# PSU.net
KiCad netlist of a schematic drawn in EAGLE
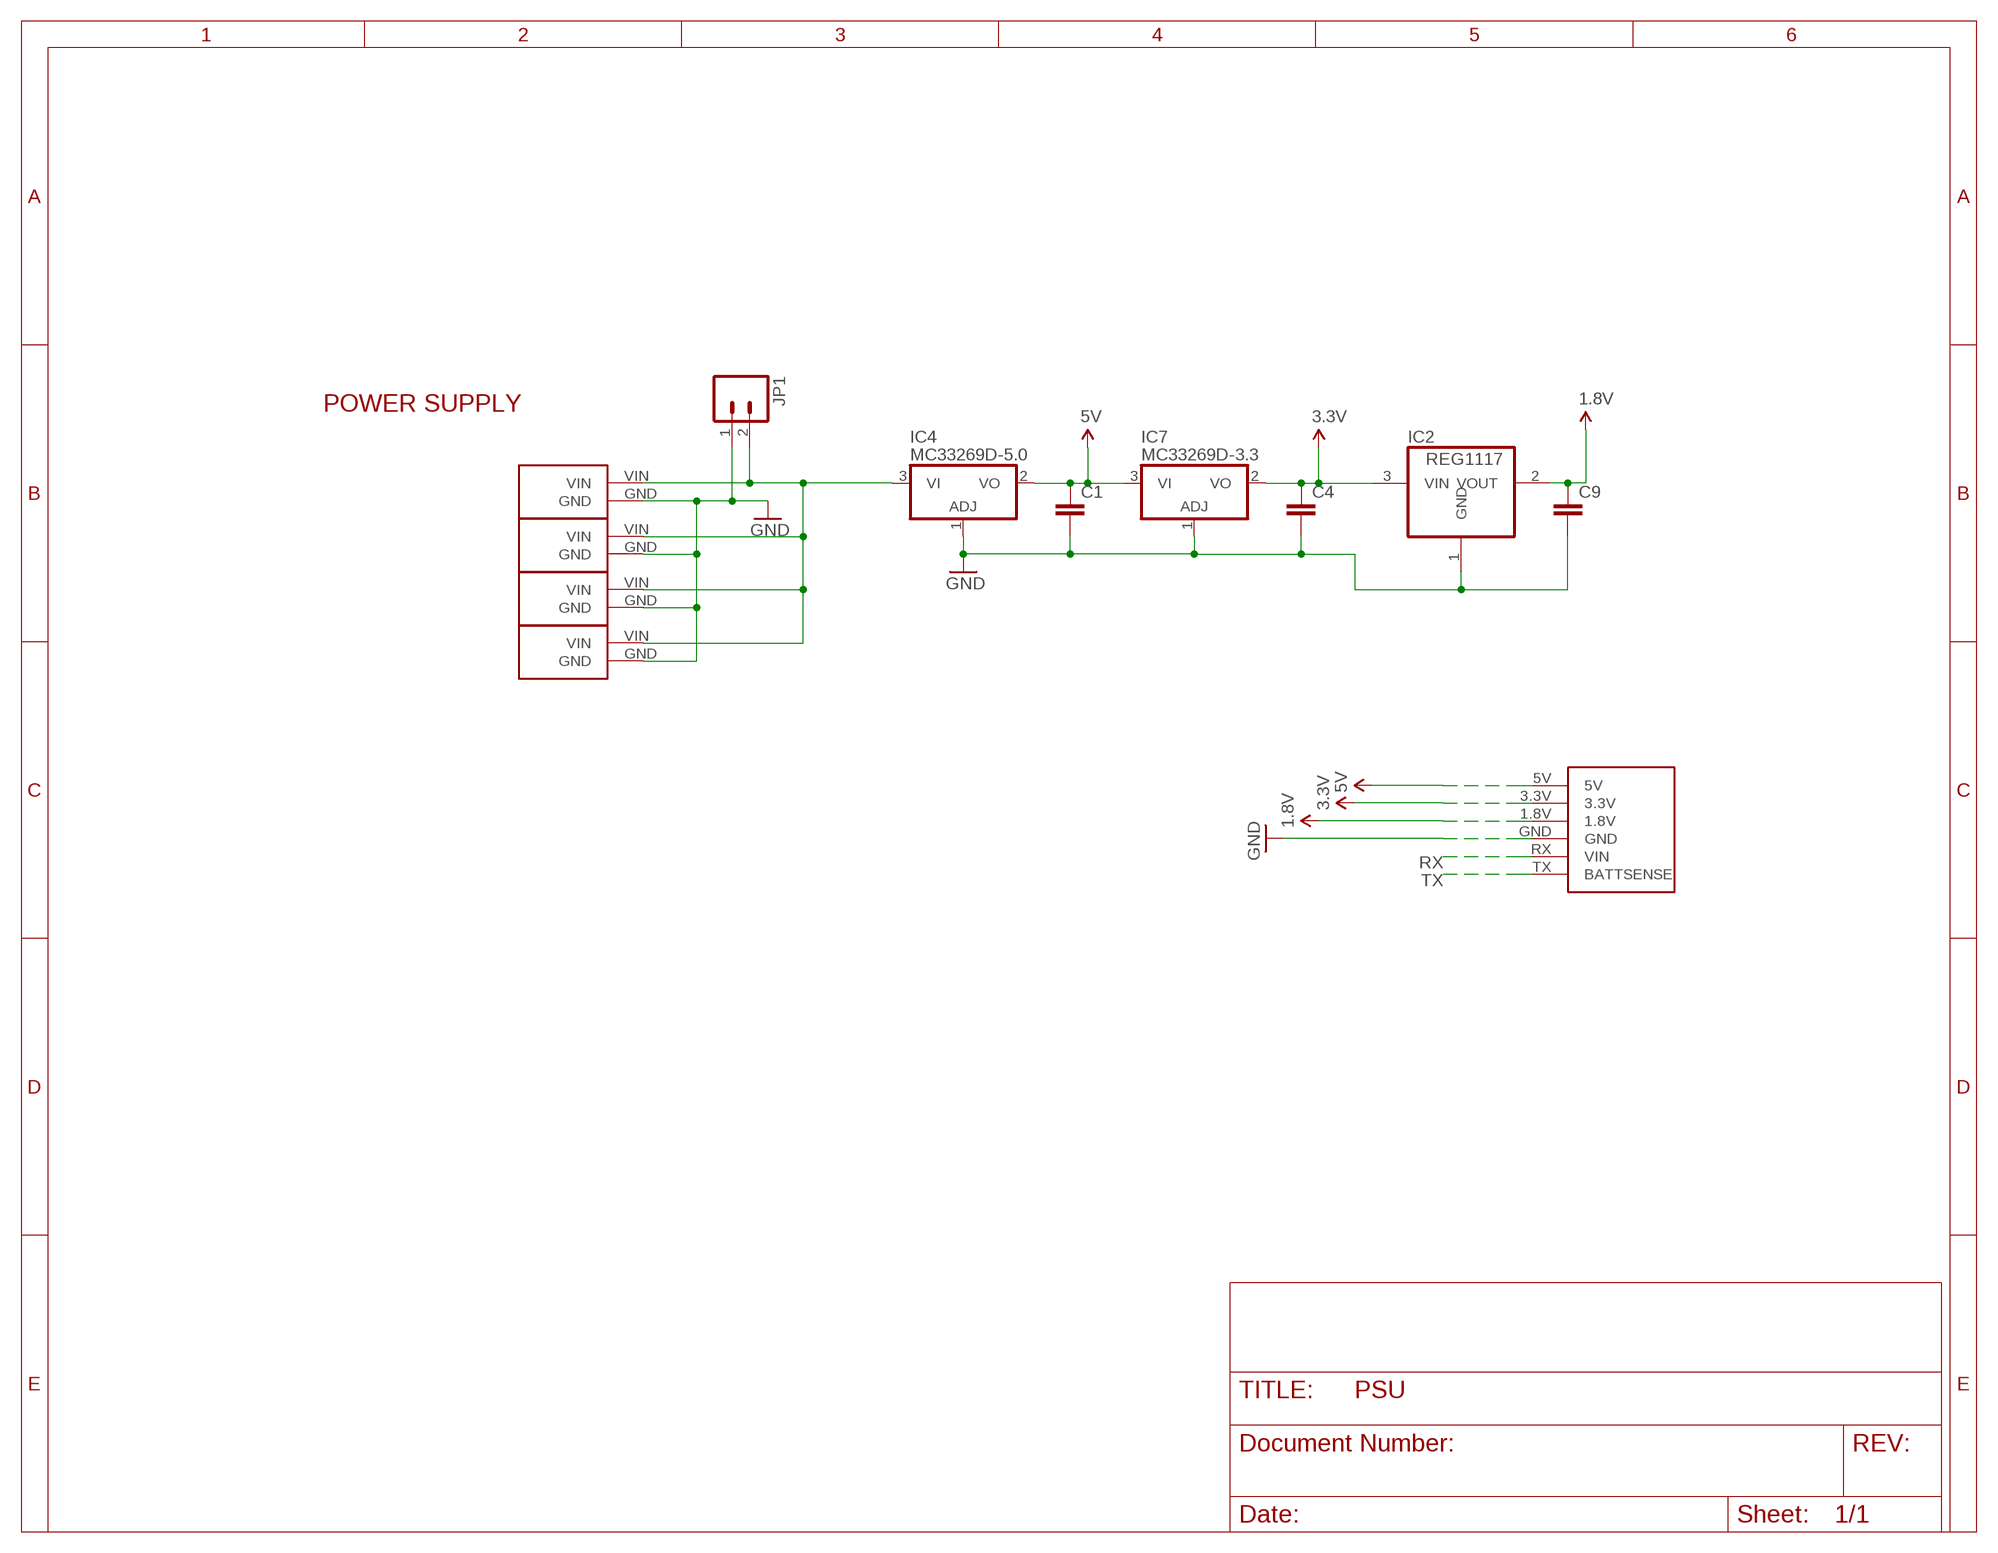
[diagram p0: schematic, sheet 1]

(export (version "E")
  (design (tool "Eeschema 10.0.6"))
  (components
    (comp (ref "C1")
      (value "CAP0805")
      (footprint "eagle-import:0805")
      (libsource (lib "eagle-import") (part "CAP0805"))
    )
    (comp (ref "C4")
      (value "CAP0805")
      (footprint "eagle-import:0805")
      (libsource (lib "eagle-import") (part "CAP0805"))
    )
    (comp (ref "C9")
      (value "CAP0805")
      (footprint "eagle-import:0805")
      (libsource (lib "eagle-import") (part "CAP0805"))
    )
    (comp (ref "IC2")
      (value "REG1117")
      (footprint "eagle-import:SOT223")
      (libsource (lib "eagle-import") (part "REG1117"))
    )
    (comp (ref "IC4")
      (value "MC33269D-5.0")
      (footprint "eagle-import:DPACK")
      (libsource (lib "eagle-import") (part "MC33269?D-5.0"))
    )
    (comp (ref "IC7")
      (value "MC33269D-3.3")
      (footprint "eagle-import:DPACK")
      (libsource (lib "eagle-import") (part "MC33269?D-3.3"))
    )
    (comp (ref "JP1")
      (value "M02PTH4")
      (footprint "eagle-import:1X02_XTRA_BIG")
      (libsource (lib "eagle-import") (part "M02PTH4"))
    )
    (comp (ref "QB1")
      (value "QUADBOARD")
      (footprint "eagle-import:QUADBOARD")
      (libsource (lib "eagle-import") (part "QUADBOARD"))
    )
    (comp (ref "U$2")
      (value "ESC_POWER")
      (footprint "eagle-import:ESCPOWER")
      (libsource (lib "eagle-import") (part "ESC_POWER"))
    )
    (comp (ref "U$3")
      (value "ESC_POWER")
      (footprint "eagle-import:ESCPOWER")
      (libsource (lib "eagle-import") (part "ESC_POWER"))
    )
    (comp (ref "U$4")
      (value "ESC_POWER")
      (footprint "eagle-import:ESCPOWER")
      (libsource (lib "eagle-import") (part "ESC_POWER"))
    )
    (comp (ref "U$5")
      (value "ESC_POWER")
      (footprint "eagle-import:ESCPOWER")
      (libsource (lib "eagle-import") (part "ESC_POWER"))
    )
  )
  (nets
    (net (code "1") (name "/RX") (class "Default")
      (node (ref "QB1") (pin "RX") (pinfunction "VIN_RX") (pintype "bidirectional"))
    )
    (net (code "2") (name "/TX") (class "Default")
      (node (ref "QB1") (pin "TX") (pinfunction "BATTSENSE_TX") (pintype "bidirectional"))
    )
    (net (code "3") (name "1.8V") (class "Default")
      (node (ref "C9") (pin "1") (pinfunction "1_1") (pintype "passive"))
      (node (ref "IC2") (pin "2") (pinfunction "VOUT_2") (pintype "output"))
      (node (ref "QB1") (pin "1.8V") (pinfunction "1.8V_1.8V") (pintype "bidirectional"))
    )
    (net (code "4") (name "3.3V") (class "Default")
      (node (ref "C4") (pin "1") (pinfunction "1_1") (pintype "passive"))
      (node (ref "IC2") (pin "3") (pinfunction "VIN_3") (pintype "input"))
      (node (ref "IC7") (pin "2") (pinfunction "VO_2") (pintype "passive"))
      (node (ref "QB1") (pin "3.3V") (pinfunction "3.3V_3.3V") (pintype "bidirectional"))
    )
    (net (code "5") (name "5V") (class "Default")
      (node (ref "C1") (pin "1") (pinfunction "1_1") (pintype "passive"))
      (node (ref "IC4") (pin "2") (pinfunction "VO_2") (pintype "passive"))
      (node (ref "IC7") (pin "3") (pinfunction "VI_3") (pintype "input"))
      (node (ref "QB1") (pin "5V") (pinfunction "5V_5V") (pintype "bidirectional"))
    )
    (net (code "6") (name "GND") (class "Default")
      (node (ref "C1") (pin "2") (pinfunction "2_2") (pintype "passive"))
      (node (ref "C4") (pin "2") (pinfunction "2_2") (pintype "passive"))
      (node (ref "C9") (pin "2") (pinfunction "2_2") (pintype "passive"))
      (node (ref "IC2") (pin "1") (pinfunction "GND_1") (pintype "power_in"))
      (node (ref "IC4") (pin "1") (pinfunction "ADJ_1") (pintype "input"))
      (node (ref "IC7") (pin "1") (pinfunction "ADJ_1") (pintype "input"))
      (node (ref "JP1") (pin "1") (pinfunction "1_1") (pintype "passive"))
      (node (ref "QB1") (pin "GND") (pinfunction "GND_GND") (pintype "bidirectional"))
      (node (ref "U$2") (pin "GND") (pinfunction "GND_GND") (pintype "bidirectional"))
      (node (ref "U$3") (pin "GND") (pinfunction "GND_GND") (pintype "bidirectional"))
      (node (ref "U$4") (pin "GND") (pinfunction "GND_GND") (pintype "bidirectional"))
      (node (ref "U$5") (pin "GND") (pinfunction "GND_GND") (pintype "bidirectional"))
    )
    (net (code "7") (name "Net-(IC4-VI)") (class "Default")
      (node (ref "IC4") (pin "3") (pinfunction "VI_3") (pintype "input"))
      (node (ref "JP1") (pin "2") (pinfunction "2_2") (pintype "passive"))
      (node (ref "U$2") (pin "VIN") (pinfunction "VIN_VIN") (pintype "bidirectional"))
      (node (ref "U$3") (pin "VIN") (pinfunction "VIN_VIN") (pintype "bidirectional"))
      (node (ref "U$4") (pin "VIN") (pinfunction "VIN_VIN") (pintype "bidirectional"))
      (node (ref "U$5") (pin "VIN") (pinfunction "VIN_VIN") (pintype "bidirectional"))
    )
  )
)
